# DCDC.net
KiCad netlist of a schematic drawn in Altium Designer
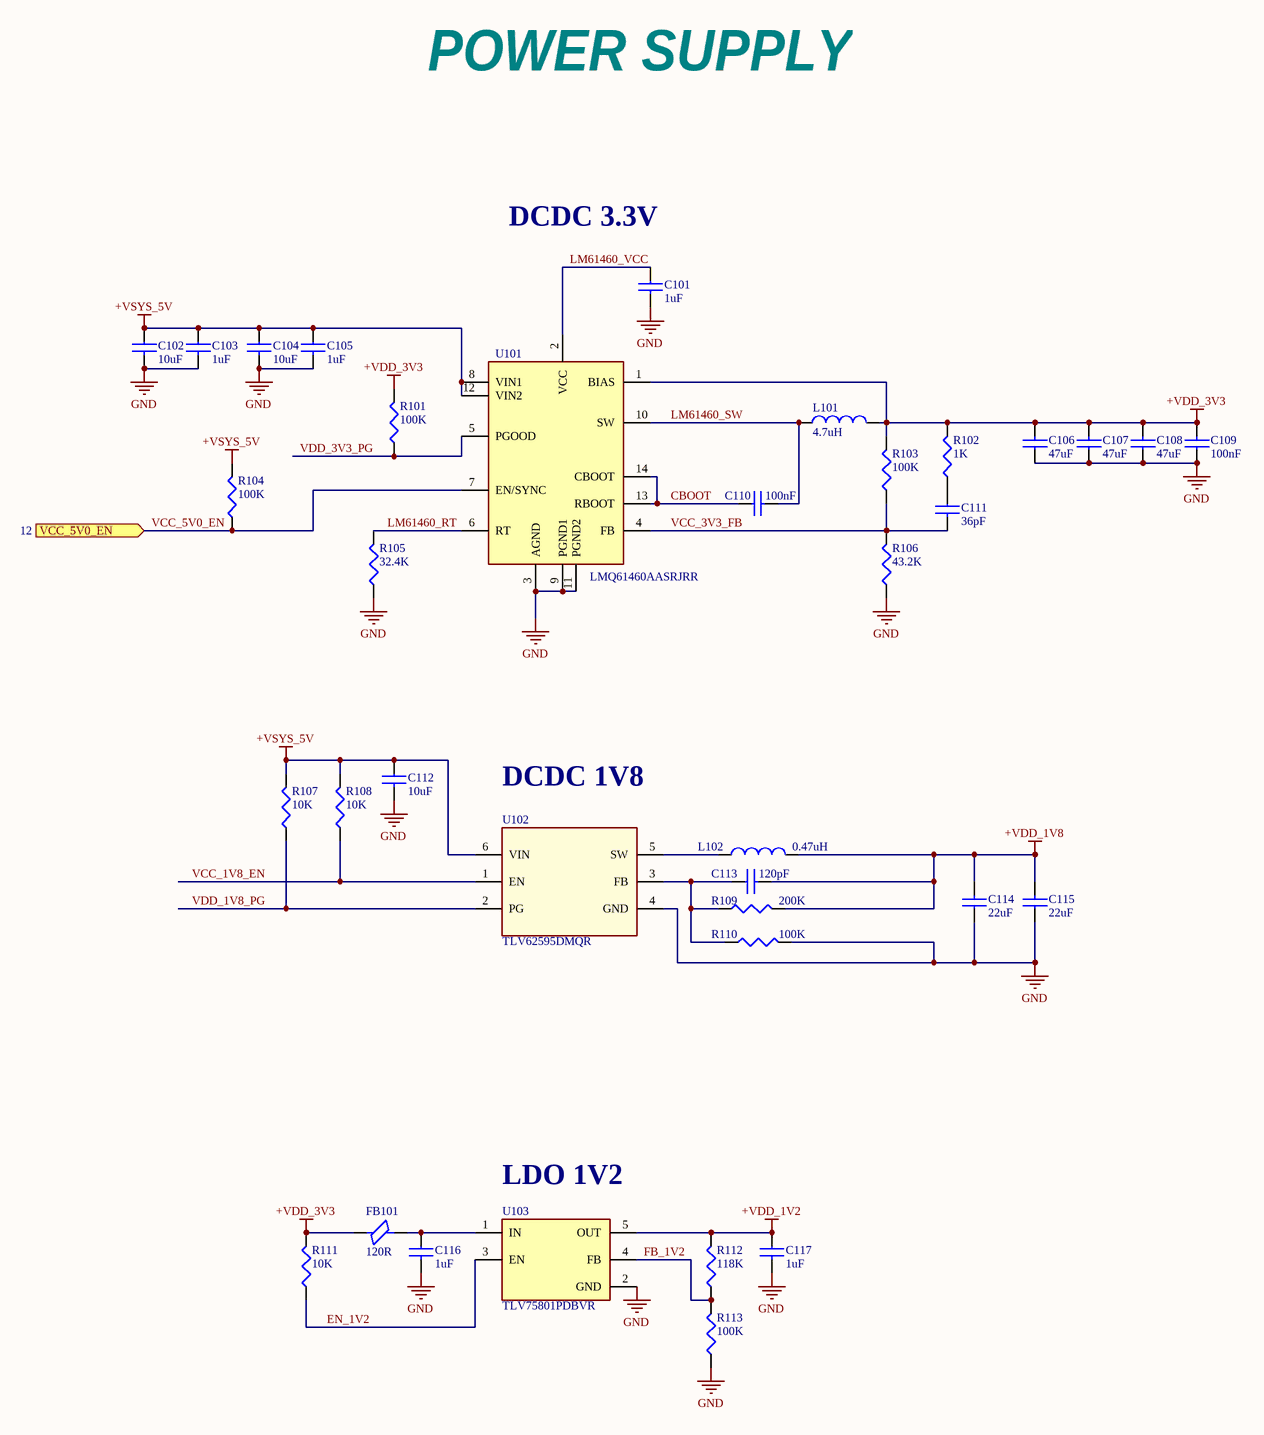
[diagram p0: DCDC.SchDoc]

(export (version "E")
  (design (tool "Eeschema 10.0.6"))
  (components
    (comp (ref "C101")
      (value "1uF")
      (footprint "C0603")
      (description "Multilayer Ceramic Capacitor, 1 uF, 16 V, ± 10%, X5R, 0603 [1608 Metric]")
      (fields
        (field (name "MANUFACTURER") "TDK")
        (field (name "MANUFACTURER PART NUMBER") "CGA3E1X5R1C105K080AC")
      )
      (libsource (lib "Schlib SOM AM625") (part "CGA3E1X5R1C105K080AC"))
    )
    (comp (ref "C102")
      (value "10uF")
      (footprint "C1206B/3216MM")
      (description "Multilayer Ceramic Capacitor, 10 uF, 16 V, ± 10%, X5R, 1206 [3216 Metric]")
      (fields
        (field (name "MANUFACTURER") "TDK")
        (field (name "MANUFACTURER PART NUMBER") "C3216X5R1C106K160AA")
      )
      (libsource (lib "Schlib SOM AM625") (part "C3216X5R1C106K160AA"))
    )
    (comp (ref "C103")
      (value "1uF")
      (footprint "C0603")
      (description "Multilayer Ceramic Capacitor, 1 uF, 16 V, ± 10%, X5R, 0603 [1608 Metric]")
      (fields
        (field (name "MANUFACTURER") "TDK")
        (field (name "MANUFACTURER PART NUMBER") "CGA3E1X5R1C105K080AC")
      )
      (libsource (lib "Schlib SOM AM625") (part "CGA3E1X5R1C105K080AC"))
    )
    (comp (ref "C104")
      (value "10uF")
      (footprint "C1206B/3216MM")
      (description "Multilayer Ceramic Capacitor, 10 uF, 16 V, ± 10%, X5R, 1206 [3216 Metric]")
      (fields
        (field (name "MANUFACTURER") "TDK")
        (field (name "MANUFACTURER PART NUMBER") "C3216X5R1C106K160AA")
      )
      (libsource (lib "Schlib SOM AM625") (part "C3216X5R1C106K160AA"))
    )
    (comp (ref "C105")
      (value "1uF")
      (footprint "C0603")
      (description "Multilayer Ceramic Capacitor, 1 uF, 16 V, ± 10%, X5R, 0603 [1608 Metric]")
      (fields
        (field (name "MANUFACTURER") "TDK")
        (field (name "MANUFACTURER PART NUMBER") "CGA3E1X5R1C105K080AC")
      )
      (libsource (lib "Schlib SOM AM625") (part "CGA3E1X5R1C105K080AC"))
    )
    (comp (ref "C106")
      (value "47uF")
      (footprint "C1206B/3216MM")
      (description "Multilayer Ceramic Capacitor, 47 uF, 16 V, ± 20%, X5R, 1206 [3216 Metric]")
      (fields
        (field (name "MANUFACTURER") "TDK")
        (field (name "MANUFACTURER PART NUMBER") "C3216X5R1C476M160AB")
      )
      (libsource (lib "Schlib SOM AM625") (part "C3216X5R1C476M160AB"))
    )
    (comp (ref "C107")
      (value "47uF")
      (footprint "C1206B/3216MM")
      (description "Multilayer Ceramic Capacitor, 47 uF, 16 V, ± 20%, X5R, 1206 [3216 Metric]")
      (fields
        (field (name "MANUFACTURER") "TDK")
        (field (name "MANUFACTURER PART NUMBER") "C3216X5R1C476M160AB")
      )
      (libsource (lib "Schlib SOM AM625") (part "C3216X5R1C476M160AB"))
    )
    (comp (ref "C108")
      (value "47uF")
      (footprint "C1206B/3216MM")
      (description "Multilayer Ceramic Capacitor, 47 uF, 16 V, ± 20%, X5R, 1206 [3216 Metric]")
      (fields
        (field (name "MANUFACTURER") "TDK")
        (field (name "MANUFACTURER PART NUMBER") "C3216X5R1C476M160AB")
      )
      (libsource (lib "Schlib SOM AM625") (part "C3216X5R1C476M160AB"))
    )
    (comp (ref "C109")
      (value "100nF")
      (footprint "C0603")
      (description "Multilayer Ceramic Capacitor, 0.1 uF, 25 V, ± 10%, X7R, 0603 [1608 Metric]")
      (fields
        (field (name "MANUFACTURER") "TDK")
        (field (name "MANUFACTURER PART NUMBER") "C1608X7R1E104K080AA")
      )
      (libsource (lib "Schlib SOM AM625") (part "C1608X7R1E104K080AA"))
    )
    (comp (ref "C110")
      (value "100nF")
      (footprint "C0603")
      (description "Multilayer Ceramic Capacitor, 0.1 uF, 25 V, ± 10%, X7R, 0603 [1608 Metric]")
      (fields
        (field (name "MANUFACTURER") "TDK")
        (field (name "MANUFACTURER PART NUMBER") "C1608X7R1E104K080AA")
      )
      (libsource (lib "Schlib SOM AM625") (part "C1608X7R1E104K080AA"))
    )
    (comp (ref "C111")
      (value "36pF")
      (footprint "C0402")
      (description "Capacitor Ceramic 36pF 50V C0G 1% 0402 Paper T/R")
      (fields
        (field (name "MANUFACTURER") "Yageo")
        (field (name "MANUFACTURER PART NUMBER") "CC0402FRNPO9BN360")
      )
      (libsource (lib "Schlib SOM AM625") (part "CC0402FRNPO9BN360"))
    )
    (comp (ref "C112")
      (value "10uF")
      (footprint "C0603")
      (description "Multilayer Ceramic Capacitor, 10 uF, 10 V, ± 10%, X5R, 0603 [1608 Metric]")
      (fields
        (field (name "MANUFACTURER") "TDK")
        (field (name "MANUFACTURER PART NUMBER") "C1608X5R1A106K080AC")
      )
      (libsource (lib "Schlib SOM AM625") (part "C1608X5R1A106K080AC"))
    )
    (comp (ref "C113")
      (value "120pF")
      (footprint "C0402")
      (description "Cap Ceramic 120pF 25V C0G 5% SMD 0402 125°C Paper T/R")
      (fields
        (field (name "MANUFACTURER") "KEMET")
        (field (name "MANUFACTURER PART NUMBER") "C0402C121J3GAC7867")
      )
      (libsource (lib "Schlib SOM AM625") (part "C0402C121J3GAC7867"))
    )
    (comp (ref "C114")
      (value "22uF")
      (footprint "C0805")
      (description "22 µF ±20% 25V Ceramic Capacitor X5R 0805 (2012 Metric)")
      (fields
        (field (name "MANUFACTURER") "Yageo")
        (field (name "MANUFACTURER PART NUMBER") "CC0805MKX5R8BB226")
      )
      (libsource (lib "Schlib SOM AM625") (part "CC0805MKX5R8BB226"))
    )
    (comp (ref "C115")
      (value "22uF")
      (footprint "C0805")
      (description "22 µF ±20% 25V Ceramic Capacitor X5R 0805 (2012 Metric)")
      (fields
        (field (name "MANUFACTURER") "Yageo")
        (field (name "MANUFACTURER PART NUMBER") "CC0805MKX5R8BB226")
      )
      (libsource (lib "Schlib SOM AM625") (part "CC0805MKX5R8BB226"))
    )
    (comp (ref "C116")
      (value "1uF")
      (footprint "C0402")
      (description "Multilayer Ceramic Capacitor, 1 uF, 16 V, ± 20%, C0G (NP0), 0201 [0603 Metric]")
      (fields
        (field (name "MANUFACTURER") "Yageo")
        (field (name "MANUFACTURER PART NUMBER") "CC0402KRX5R6BB105")
      )
      (libsource (lib "Schlib SOM AM625") (part "CC0402KRX5R6BB105"))
    )
    (comp (ref "C117")
      (value "1uF")
      (footprint "C0402")
      (description "Multilayer Ceramic Capacitor, 1 uF, 16 V, ± 20%, C0G (NP0), 0201 [0603 Metric]")
      (fields
        (field (name "MANUFACTURER") "Yageo")
        (field (name "MANUFACTURER PART NUMBER") "CC0402KRX5R6BB105")
      )
      (libsource (lib "Schlib SOM AM625") (part "CC0402KRX5R6BB105"))
    )
    (comp (ref "FB101")
      (value "120R")
      (footprint "FB0402")
      (description "Ferrite Beads Multi-Layer 120Ohm 25% 100MHz 1.3A 0.09Ohm DCR 0402 Automotive T/R")
      (fields
        (field (name "MANUFACTURER") "Murata")
        (field (name "MANUFACTURER PART NUMBER") "BLM15PD121SZ1D")
      )
      (libsource (lib "Schlib SOM AM625") (part "BLM15PD121SZ1D"))
    )
    (comp (ref "L101")
      (value "4.7uH")
      (footprint "IND_WE-XHMI_8080_WRE")
      (description "Fixed Ind 4.7UH 9.5A 8.65 Mohm")
      (fields
        (field (name "MANUFACTURER") "Wurth Electronics")
        (field (name "MANUFACTURER PART NUMBER") "74439358047")
      )
      (libsource (lib "Schlib SOM AM625") (part "74439358047"))
    )
    (comp (ref "L102")
      (value "0.47uH")
      (footprint "l2016")
      (description "Inductor Power Shielded Wirewound 0.47uH 20% 1MHz Metal 3.6A 0.032Ohm DCR 0806 T/R")
      (fields
        (field (name "MANUFACTURER") "Murata")
        (field (name "MANUFACTURER PART NUMBER") "DFE201610E-R47M=P2")
      )
      (libsource (lib "Schlib SOM AM625") (part "DFE201610E-R47M=P2"))
    )
    (comp (ref "R101")
      (value "100K")
      (footprint "R0402")
      (description "SMD Chip Resistor, 100 kOhm, ± 1%, 63 mW, 0402 [1005 Metric], Thick Film, General Purpose")
      (fields
        (field (name "MANUFACTURER") "Yageo")
        (field (name "MANUFACTURER PART NUMBER") "RC0402FR-07100KL")
      )
      (libsource (lib "Schlib SOM AM625") (part "RC0402FR-07100KL"))
    )
    (comp (ref "R102")
      (value "1K")
      (footprint "R0402")
      (description "SMD Chip Resistor, 1 kOhm, ± 1%, 63 mW, 0402 [1005 Metric], Thick Film, General Purpose")
      (fields
        (field (name "MANUFACTURER") "Yageo")
        (field (name "MANUFACTURER PART NUMBER") "RC0402FR-071KL")
      )
      (libsource (lib "Schlib SOM AM625") (part "RC0402FR-071KL"))
    )
    (comp (ref "R103")
      (value "100K")
      (footprint "R0402")
      (description "SMD Chip Resistor, 100 kOhm, ± 1%, 63 mW, 0402 [1005 Metric], Thick Film, General Purpose")
      (fields
        (field (name "MANUFACTURER") "Yageo")
        (field (name "MANUFACTURER PART NUMBER") "RC0402FR-07100KL")
      )
      (libsource (lib "Schlib SOM AM625") (part "RC0402FR-07100KL"))
    )
    (comp (ref "R104")
      (value "100K")
      (footprint "R0402")
      (description "SMD Chip Resistor, 100 kOhm, ± 1%, 63 mW, 0402 [1005 Metric], Thick Film, General Purpose")
      (fields
        (field (name "MANUFACTURER") "Yageo")
        (field (name "MANUFACTURER PART NUMBER") "RC0402FR-07100KL")
      )
      (libsource (lib "Schlib SOM AM625") (part "RC0402FR-07100KL"))
    )
    (comp (ref "R105")
      (value "32.4K")
      (footprint "R0402")
      (description "SMD Chip Resistor, 32.4 kOhm, ± 1%, 63 mW, 0402 [1005 Metric], Thick Film, General Purpose")
      (fields
        (field (name "MANUFACTURER") "Yageo")
        (field (name "MANUFACTURER PART NUMBER") "RC0402FR-0732K4L")
      )
      (libsource (lib "Schlib SOM AM625") (part "RC0402FR-0732K4L"))
    )
    (comp (ref "R106")
      (value "43.2K")
      (footprint "R0402")
      (description "SMD Chip Resistor, 43.2 kOhm, ± 1%, 63 mW, 0402 [1005 Metric], Thick Film, General Purpose")
      (fields
        (field (name "MANUFACTURER") "Yageo")
        (field (name "MANUFACTURER PART NUMBER") "RC0402FR-0743K2L")
      )
      (libsource (lib "Schlib SOM AM625") (part "RC0402FR-0743K2L"))
    )
    (comp (ref "R107")
      (value "10K")
      (footprint "R0402")
      (description "RES 10.0K OHM 1/16W 1% 0402 SMD")
      (fields
        (field (name "MANUFACTURER") "Yageo")
        (field (name "MANUFACTURER PART NUMBER") "RC0402FR-0710KL")
      )
      (libsource (lib "Schlib SOM AM625") (part "RC0402FR-0710KL"))
    )
    (comp (ref "R108")
      (value "10K")
      (footprint "R0402")
      (description "RES 10.0K OHM 1/16W 1% 0402 SMD")
      (fields
        (field (name "MANUFACTURER") "Yageo")
        (field (name "MANUFACTURER PART NUMBER") "RC0402FR-0710KL")
      )
      (libsource (lib "Schlib SOM AM625") (part "RC0402FR-0710KL"))
    )
    (comp (ref "R109")
      (value "200K")
      (footprint "R0402")
      (description "SMD Chip Resistor, 200 kOhm, ± 1%, 63 mW, 0402 [1005 Metric], Thick Film, General Purpose")
      (fields
        (field (name "MANUFACTURER") "Yageo")
        (field (name "MANUFACTURER PART NUMBER") "RC0402FR-07200KL")
      )
      (libsource (lib "Schlib SOM AM625") (part "RC0402FR-07200KL"))
    )
    (comp (ref "R110")
      (value "100K")
      (footprint "R0402")
      (description "SMD Chip Resistor, 100 kOhm, ± 1%, 63 mW, 0402 [1005 Metric], Thick Film, General Purpose")
      (fields
        (field (name "MANUFACTURER") "Yageo")
        (field (name "MANUFACTURER PART NUMBER") "AC0402FR-07100KL")
      )
      (libsource (lib "Schlib SOM AM625") (part "AC0402FR-07100KL"))
    )
    (comp (ref "R111")
      (value "10K")
      (footprint "R0402")
      (description "RES 10.0K OHM 1/16W 1% 0402 SMD")
      (fields
        (field (name "MANUFACTURER") "Yageo")
        (field (name "MANUFACTURER PART NUMBER") "RC0402FR-0710KL")
      )
      (libsource (lib "Schlib SOM AM625") (part "RC0402FR-0710KL"))
    )
    (comp (ref "R112")
      (value "118K")
      (footprint "R0402")
      (description "SMD Chip Resistor, 118 kOhm, ± 1%, 63 mW, 0402 [1005 Metric], Thick Film, General Purpose")
      (fields
        (field (name "MANUFACTURER") "Yageo")
        (field (name "MANUFACTURER PART NUMBER") "RC0402FR-07118KL")
      )
      (libsource (lib "Schlib SOM AM625") (part "RC0402FR-07118KL"))
    )
    (comp (ref "R113")
      (value "100K")
      (footprint "R0402")
      (description "SMD Chip Resistor, 100 kOhm, ± 1%, 63 mW, 0402 [1005 Metric], Thick Film, General Purpose")
      (fields
        (field (name "MANUFACTURER") "Yageo")
        (field (name "MANUFACTURER PART NUMBER") "AC0402FR-07100KL")
      )
      (libsource (lib "Schlib SOM AM625") (part "AC0402FR-07100KL"))
    )
    (comp (ref "U101")
      (value "LMQ61460AASRJRR")
      (footprint "14-VFQFN")
      (description "Industrial 3-V to 36-V, 6-A, low-noise synchronous step-down converter 14-VQFN-HR -40 to 150")
      (fields (field (name "MANUFACTURER") "Texas Instruments"))
      (libsource (lib "Schlib SOM AM625") (part "LMQ61460AASRJRR"))
    )
    (comp (ref "U102")
      (value "TLV62595DMQR")
      (footprint "VSON6_0D5_1D5X1D5X1MM")
      (fields (field (name "MANUFACTURER") "Texas Instruments"))
      (libsource (lib "Schlib SOM AM625") (part "TLV62595DMQR"))
    )
    (comp (ref "U103")
      (value "TLV75801PDBVR")
      (footprint "SOT23-5")
      (description "Adjustable 500-mA low-dropout (LDO) regulator 5-SOT-23 -40 to 125")
      (fields (field (name "MANUFACTURER") "Texas Instruments"))
      (libsource (lib "Schlib SOM AM625") (part "TLV75801PDBVR"))
    )
  )
  (nets
    (net (code "1") (name "+VDD_1V2") (class "Default")
      (node (ref "C117") (pin "1") (pinfunction "1_1") (pintype "passive"))
      (node (ref "R112") (pin "2") (pinfunction "2_2") (pintype "passive"))
      (node (ref "U103") (pin "5") (pinfunction "OUT_5") (pintype "passive"))
    )
    (net (code "2") (name "+VDD_1V8") (class "Default")
      (node (ref "C113") (pin "2") (pinfunction "2_2") (pintype "passive"))
      (node (ref "C114") (pin "2") (pinfunction "2_2") (pintype "passive"))
      (node (ref "C115") (pin "2") (pinfunction "2_2") (pintype "passive"))
      (node (ref "L102") (pin "2") (pinfunction "2_2") (pintype "passive"))
      (node (ref "R109") (pin "2") (pinfunction "2_2") (pintype "passive"))
    )
    (net (code "3") (name "+VDD_3V3") (class "Default")
      (node (ref "C106") (pin "2") (pinfunction "2_2") (pintype "passive"))
      (node (ref "C107") (pin "2") (pinfunction "2_2") (pintype "passive"))
      (node (ref "C108") (pin "2") (pinfunction "2_2") (pintype "passive"))
      (node (ref "C109") (pin "2") (pinfunction "2_2") (pintype "passive"))
      (node (ref "FB101") (pin "1") (pinfunction "1_1") (pintype "passive"))
      (node (ref "L101") (pin "2") (pinfunction "2_2") (pintype "passive"))
      (node (ref "R101") (pin "2") (pinfunction "2_2") (pintype "passive"))
      (node (ref "R102") (pin "2") (pinfunction "2_2") (pintype "passive"))
      (node (ref "R103") (pin "2") (pinfunction "2_2") (pintype "passive"))
      (node (ref "R111") (pin "2") (pinfunction "2_2") (pintype "passive"))
      (node (ref "U101") (pin "1") (pinfunction "BIAS_1") (pintype "passive"))
    )
    (net (code "4") (name "+VSYS_5V") (class "Default")
      (node (ref "C102") (pin "1") (pinfunction "1_1") (pintype "passive"))
      (node (ref "C103") (pin "1") (pinfunction "1_1") (pintype "passive"))
      (node (ref "C104") (pin "1") (pinfunction "1_1") (pintype "passive"))
      (node (ref "C105") (pin "1") (pinfunction "1_1") (pintype "passive"))
      (node (ref "C112") (pin "1") (pinfunction "1_1") (pintype "passive"))
      (node (ref "R104") (pin "2") (pinfunction "2_2") (pintype "passive"))
      (node (ref "R107") (pin "2") (pinfunction "2_2") (pintype "passive"))
      (node (ref "R108") (pin "2") (pinfunction "2_2") (pintype "passive"))
      (node (ref "U101") (pin "12") (pinfunction "VIN2_12") (pintype "passive"))
      (node (ref "U101") (pin "8") (pinfunction "VIN1_8") (pintype "passive"))
      (node (ref "U102") (pin "6") (pinfunction "VIN_6") (pintype "power_in"))
    )
    (net (code "5") (name "/CBOOT") (class "Default")
      (node (ref "C110") (pin "1") (pinfunction "1_1") (pintype "passive"))
      (node (ref "U101") (pin "13") (pinfunction "RBOOT_13") (pintype "passive"))
      (node (ref "U101") (pin "14") (pinfunction "CBOOT_14") (pintype "passive"))
    )
    (net (code "6") (name "/EN_1V2") (class "Default")
      (node (ref "R111") (pin "1") (pinfunction "1_1") (pintype "passive"))
      (node (ref "U103") (pin "3") (pinfunction "EN_3") (pintype "passive"))
    )
    (net (code "7") (name "/FB_1V2") (class "Default")
      (node (ref "R112") (pin "1") (pinfunction "1_1") (pintype "passive"))
      (node (ref "R113") (pin "2") (pinfunction "2_2") (pintype "passive"))
      (node (ref "U103") (pin "4") (pinfunction "FB_4") (pintype "passive"))
    )
    (net (code "8") (name "/LM61460_RT") (class "Default")
      (node (ref "R105") (pin "2") (pinfunction "2_2") (pintype "passive"))
      (node (ref "U101") (pin "6") (pinfunction "RT_6") (pintype "passive"))
    )
    (net (code "9") (name "/LM61460_SW") (class "Default")
      (node (ref "C110") (pin "2") (pinfunction "2_2") (pintype "passive"))
      (node (ref "L101") (pin "1") (pinfunction "1_1") (pintype "passive"))
      (node (ref "U101") (pin "10") (pinfunction "SW_10") (pintype "passive"))
    )
    (net (code "10") (name "/LM61460_VCC") (class "Default")
      (node (ref "C101") (pin "1") (pinfunction "1_1") (pintype "passive"))
      (node (ref "U101") (pin "2") (pinfunction "VCC_2") (pintype "passive"))
    )
    (net (code "11") (name "/VCC_1V8_EN") (class "Default")
      (node (ref "R108") (pin "1") (pinfunction "1_1") (pintype "passive"))
      (node (ref "U102") (pin "1") (pinfunction "EN_1") (pintype "passive"))
    )
    (net (code "12") (name "/VCC_3V3_FB") (class "Default")
      (node (ref "C111") (pin "2") (pinfunction "2_2") (pintype "passive"))
      (node (ref "R103") (pin "1") (pinfunction "1_1") (pintype "passive"))
      (node (ref "R106") (pin "2") (pinfunction "2_2") (pintype "passive"))
      (node (ref "U101") (pin "4") (pinfunction "FB_4") (pintype "passive"))
    )
    (net (code "13") (name "/VCC_5V0_EN") (class "Default")
      (node (ref "R104") (pin "1") (pinfunction "1_1") (pintype "passive"))
      (node (ref "U101") (pin "7") (pinfunction "EN/SYNC_7") (pintype "passive"))
    )
    (net (code "14") (name "/VDD_1V8_PG") (class "Default")
      (node (ref "R107") (pin "1") (pinfunction "1_1") (pintype "passive"))
      (node (ref "U102") (pin "2") (pinfunction "PG_2") (pintype "open_collector"))
    )
    (net (code "15") (name "/VDD_3V3_PG") (class "Default")
      (node (ref "R101") (pin "1") (pinfunction "1_1") (pintype "passive"))
      (node (ref "U101") (pin "5") (pinfunction "PGOOD_5") (pintype "passive"))
    )
    (net (code "16") (name "GND") (class "Default")
      (node (ref "C101") (pin "2") (pinfunction "2_2") (pintype "passive"))
      (node (ref "C102") (pin "2") (pinfunction "2_2") (pintype "passive"))
      (node (ref "C103") (pin "2") (pinfunction "2_2") (pintype "passive"))
      (node (ref "C104") (pin "2") (pinfunction "2_2") (pintype "passive"))
      (node (ref "C105") (pin "2") (pinfunction "2_2") (pintype "passive"))
      (node (ref "C106") (pin "1") (pinfunction "1_1") (pintype "passive"))
      (node (ref "C107") (pin "1") (pinfunction "1_1") (pintype "passive"))
      (node (ref "C108") (pin "1") (pinfunction "1_1") (pintype "passive"))
      (node (ref "C109") (pin "1") (pinfunction "1_1") (pintype "passive"))
      (node (ref "C112") (pin "2") (pinfunction "2_2") (pintype "passive"))
      (node (ref "C114") (pin "1") (pinfunction "1_1") (pintype "passive"))
      (node (ref "C115") (pin "1") (pinfunction "1_1") (pintype "passive"))
      (node (ref "C116") (pin "2") (pinfunction "2_2") (pintype "passive"))
      (node (ref "C117") (pin "2") (pinfunction "2_2") (pintype "passive"))
      (node (ref "R105") (pin "1") (pinfunction "1_1") (pintype "passive"))
      (node (ref "R106") (pin "1") (pinfunction "1_1") (pintype "passive"))
      (node (ref "R110") (pin "2") (pinfunction "2_2") (pintype "passive"))
      (node (ref "R113") (pin "1") (pinfunction "1_1") (pintype "passive"))
      (node (ref "U101") (pin "11") (pinfunction "PGND2_11") (pintype "passive"))
      (node (ref "U101") (pin "3") (pinfunction "AGND_3") (pintype "passive"))
      (node (ref "U101") (pin "9") (pinfunction "PGND1_9") (pintype "passive"))
      (node (ref "U102") (pin "4") (pinfunction "GND_4") (pintype "power_in"))
      (node (ref "U103") (pin "2") (pinfunction "GND_2") (pintype "power_in"))
    )
    (net (code "17") (name "Net-(C111-Pad1)") (class "Default")
      (node (ref "C111") (pin "1") (pinfunction "1_1") (pintype "passive"))
      (node (ref "R102") (pin "1") (pinfunction "1_1") (pintype "passive"))
    )
    (net (code "18") (name "Net-(U102-FB)") (class "Default")
      (node (ref "C113") (pin "1") (pinfunction "1_1") (pintype "passive"))
      (node (ref "R109") (pin "1") (pinfunction "1_1") (pintype "passive"))
      (node (ref "R110") (pin "1") (pinfunction "1_1") (pintype "passive"))
      (node (ref "U102") (pin "3") (pinfunction "FB_3") (pintype "passive"))
    )
    (net (code "19") (name "Net-(U102-SW)") (class "Default")
      (node (ref "L102") (pin "1") (pinfunction "1_1") (pintype "passive"))
      (node (ref "U102") (pin "5") (pinfunction "SW_5") (pintype "passive"))
    )
    (net (code "20") (name "Net-(U103-IN)") (class "Default")
      (node (ref "C116") (pin "1") (pinfunction "1_1") (pintype "passive"))
      (node (ref "FB101") (pin "2") (pinfunction "2_2") (pintype "passive"))
      (node (ref "U103") (pin "1") (pinfunction "IN_1") (pintype "passive"))
    )
  )
)
